# Connectors.net
KiCad netlist of a schematic drawn in Altium Designer
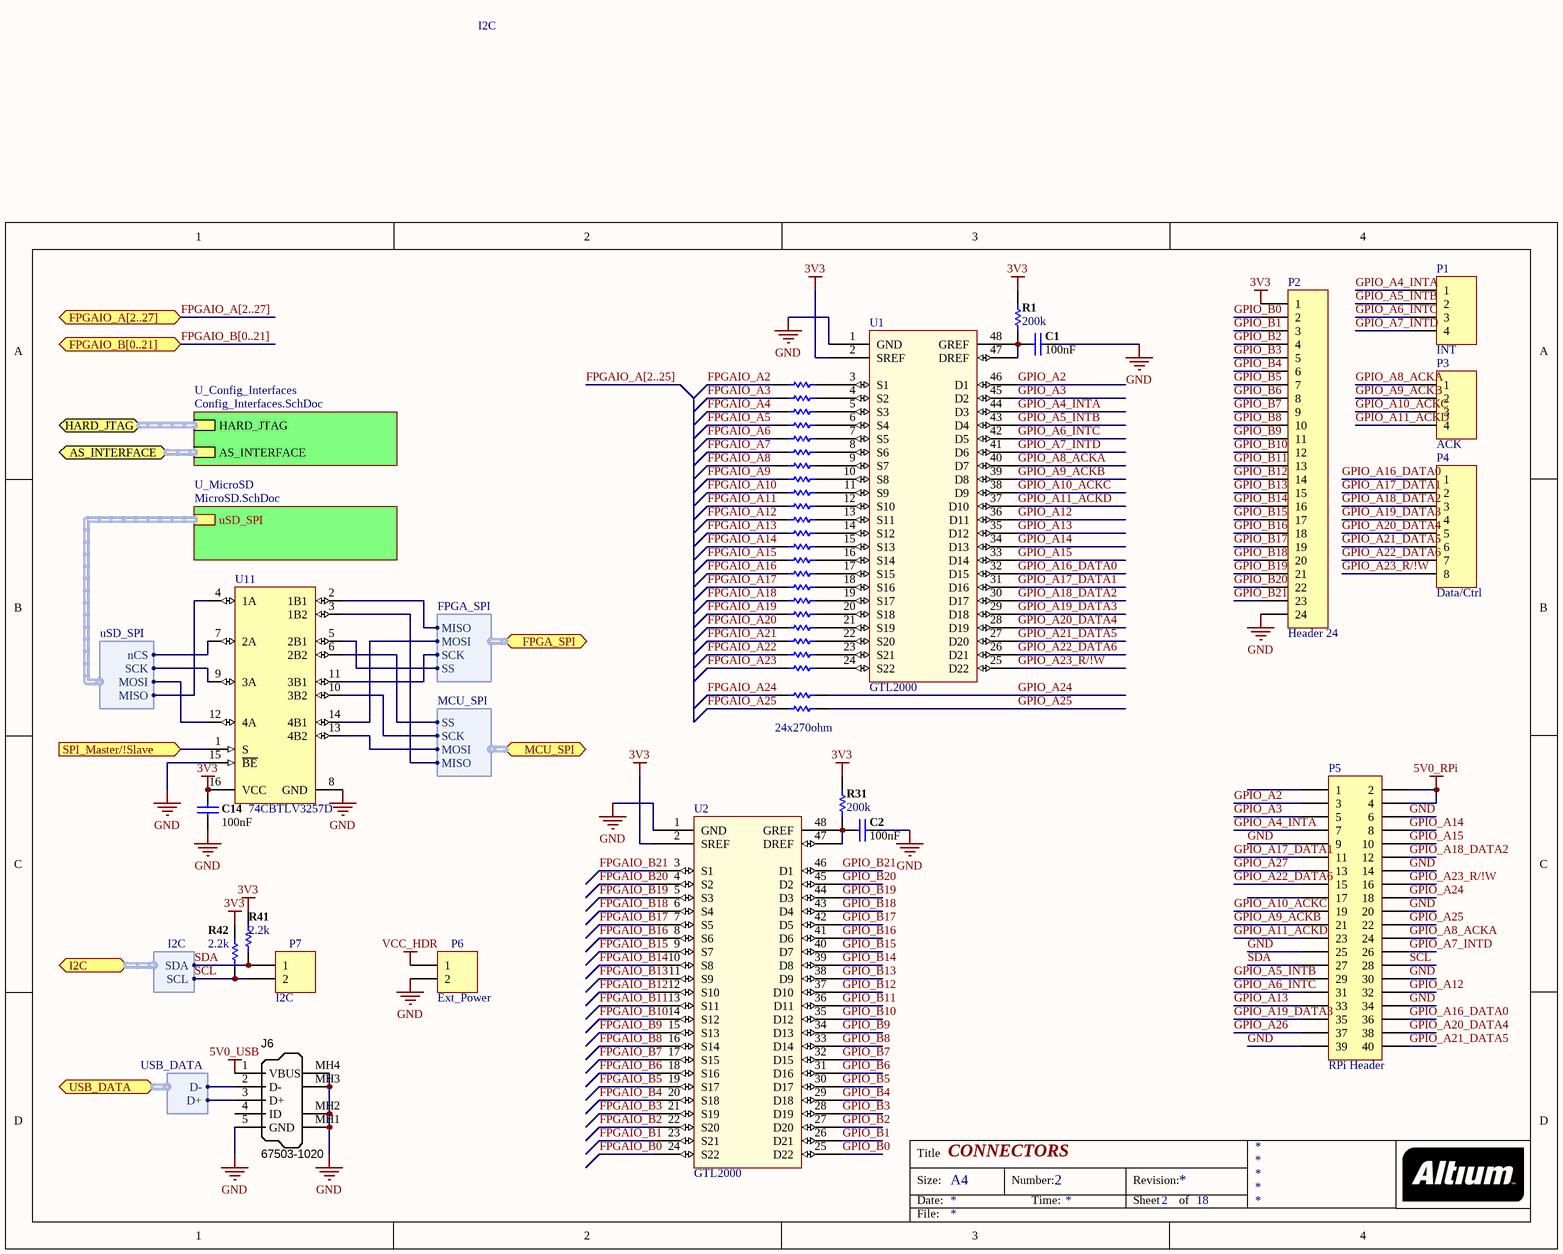
[diagram p0: Connectors.SchDoc]

(export (version "E")
  (design (tool "Eeschema 10.0.6"))
  (components
    (comp (ref "C1")
      (value "100nF")
      (footprint "0805C-GENERIC")
      (description "Capacitor, Ceramic, 10% 10V 0805 X7R")
      (fields (field (name "CAPACITANCE") "100nF") (field (name "TOLERANCE") "10 %"))
      (libsource (lib "altium-import") (part "root_1_CAP-NP_"))
    )
    (comp (ref "C2")
      (value "100nF")
      (footprint "0805C-GENERIC")
      (description "Capacitor, Ceramic, 10% 10V 0805 X7R")
      (fields (field (name "CAPACITANCE") "100nF") (field (name "TOLERANCE") "10 %"))
      (libsource (lib "altium-import") (part "root_1_CAP-NP_"))
    )
    (comp (ref "C14")
      (value "100nF")
      (footprint "0805C-GENERIC")
      (description "Capacitor, Ceramic, 10% 10V 0805 X7R")
      (fields (field (name "CAPACITANCE") "100nF") (field (name "TOLERANCE") "10 %"))
      (libsource (lib "altium-import") (part "root_0_CAP-NP_"))
    )
    (comp (ref "J6")
      (value "USB_Mini-B")
      (footprint "USB_Mini-B_Molex_SMT")
      (description "Connector SMD USB Type Mini-B")
      (fields (field (name "MANUFACTURER PART NUMBER 1") "67503-1020"))
      (libsource (lib "PBL - Connectors") (part "USB_Mini-B"))
    )
    (comp (ref "P1")
      (value "Header 4")
      (footprint "HEADER-1X4")
      (description "Header, 4-Pin")
      (fields (field (name "PUBLISHER") "Altium Limited"))
      (libsource (lib "Miscellaneous Connectors") (part "Header 4"))
    )
    (comp (ref "P2")
      (value "Header 24")
      (footprint "HDR1X24")
      (description "Header, 24-Pin")
      (fields (field (name "PUBLISHER") "Altium Limited"))
      (libsource (lib "Miscellaneous Connectors") (part "Header 24"))
    )
    (comp (ref "P3")
      (value "Header 4")
      (footprint "HEADER-1X4")
      (description "Header, 4-Pin")
      (fields (field (name "PUBLISHER") "Altium Limited"))
      (libsource (lib "Miscellaneous Connectors") (part "Header 4"))
    )
    (comp (ref "P4")
      (value "Header 8")
      (footprint "HEADER-1X8")
      (description "Header, 8-Pin")
      (fields (field (name "PUBLISHER") "Altium Limited"))
      (libsource (lib "Miscellaneous Connectors") (part "Header 8"))
    )
    (comp (ref "P5")
      (value "Header 20X2")
      (description "Header, 20-Pin, Dual row")
      (fields (field (name "PUBLISHER") "Altium Limited"))
      (libsource (lib "Miscellaneous Connectors") (part "Header 20X2"))
    )
    (comp (ref "P6")
      (value "Header 2")
      (footprint "Connector Molex 2")
      (description "Header, 2-Pin")
      (fields (field (name "PUBLISHER") "Altium Limited"))
      (libsource (lib "Miscellaneous Connectors") (part "Header 2"))
    )
    (comp (ref "P7")
      (value "Header 2")
      (footprint "HEADER-1X2")
      (description "Header, 2-Pin")
      (fields (field (name "PUBLISHER") "Altium Limited"))
      (libsource (lib "Miscellaneous Connectors") (part "Header 2"))
    )
    (comp (ref "R1")
      (value "200k")
      (footprint "0805R-220K")
      (fields (field (name "TOLERANCE") "1 %"))
      (libsource (lib "AltiumDesignLibrary") (part "RES"))
    )
    (comp (ref "R2")
      (value "270")
      (footprint "0805R-270")
      (fields (field (name "TOLERANCE") "1 %"))
      (libsource (lib "AltiumDesignLibrary") (part "RES"))
    )
    (comp (ref "R5")
      (value "270")
      (footprint "0805R-270")
      (fields (field (name "TOLERANCE") "1 %"))
      (libsource (lib "AltiumDesignLibrary") (part "RES"))
    )
    (comp (ref "R14")
      (value "270")
      (footprint "0805R-270")
      (fields (field (name "TOLERANCE") "1 %"))
      (libsource (lib "AltiumDesignLibrary") (part "RES"))
    )
    (comp (ref "R15")
      (value "270")
      (footprint "0805R-270")
      (fields (field (name "TOLERANCE") "1 %"))
      (libsource (lib "AltiumDesignLibrary") (part "RES"))
    )
    (comp (ref "R16")
      (value "270")
      (footprint "0805R-270")
      (fields (field (name "TOLERANCE") "1 %"))
      (libsource (lib "AltiumDesignLibrary") (part "RES"))
    )
    (comp (ref "R17")
      (value "270")
      (footprint "0805R-270")
      (fields (field (name "TOLERANCE") "1 %"))
      (libsource (lib "AltiumDesignLibrary") (part "RES"))
    )
    (comp (ref "R18")
      (value "270")
      (footprint "0805R-270")
      (fields (field (name "TOLERANCE") "1 %"))
      (libsource (lib "AltiumDesignLibrary") (part "RES"))
    )
    (comp (ref "R19")
      (value "270")
      (footprint "0805R-270")
      (fields (field (name "TOLERANCE") "1 %"))
      (libsource (lib "AltiumDesignLibrary") (part "RES"))
    )
    (comp (ref "R20")
      (value "270")
      (footprint "0805R-270")
      (fields (field (name "TOLERANCE") "1 %"))
      (libsource (lib "AltiumDesignLibrary") (part "RES"))
    )
    (comp (ref "R21")
      (value "270")
      (footprint "0805R-270")
      (fields (field (name "TOLERANCE") "1 %"))
      (libsource (lib "AltiumDesignLibrary") (part "RES"))
    )
    (comp (ref "R22")
      (value "270")
      (footprint "0805R-270")
      (fields (field (name "TOLERANCE") "1 %"))
      (libsource (lib "AltiumDesignLibrary") (part "RES"))
    )
    (comp (ref "R23")
      (value "270")
      (footprint "0805R-270")
      (fields (field (name "TOLERANCE") "1 %"))
      (libsource (lib "AltiumDesignLibrary") (part "RES"))
    )
    (comp (ref "R24")
      (value "270")
      (footprint "0805R-270")
      (fields (field (name "TOLERANCE") "1 %"))
      (libsource (lib "AltiumDesignLibrary") (part "RES"))
    )
    (comp (ref "R25")
      (value "270")
      (footprint "0805R-270")
      (fields (field (name "TOLERANCE") "1 %"))
      (libsource (lib "AltiumDesignLibrary") (part "RES"))
    )
    (comp (ref "R26")
      (value "270")
      (footprint "0805R-270")
      (fields (field (name "TOLERANCE") "1 %"))
      (libsource (lib "AltiumDesignLibrary") (part "RES"))
    )
    (comp (ref "R27")
      (value "270")
      (footprint "0805R-270")
      (fields (field (name "TOLERANCE") "1 %"))
      (libsource (lib "AltiumDesignLibrary") (part "RES"))
    )
    (comp (ref "R28")
      (value "270")
      (footprint "0805R-270")
      (fields (field (name "TOLERANCE") "1 %"))
      (libsource (lib "AltiumDesignLibrary") (part "RES"))
    )
    (comp (ref "R29")
      (value "270")
      (footprint "0805R-270")
      (fields (field (name "TOLERANCE") "1 %"))
      (libsource (lib "AltiumDesignLibrary") (part "RES"))
    )
    (comp (ref "R30")
      (value "270")
      (footprint "0805R-270")
      (fields (field (name "TOLERANCE") "1 %"))
      (libsource (lib "AltiumDesignLibrary") (part "RES"))
    )
    (comp (ref "R31")
      (value "200k")
      (footprint "0805R-220K")
      (fields (field (name "TOLERANCE") "1 %"))
      (libsource (lib "AltiumDesignLibrary") (part "RES"))
    )
    (comp (ref "R35")
      (value "270")
      (footprint "0805R-270")
      (fields (field (name "TOLERANCE") "1 %"))
      (libsource (lib "AltiumDesignLibrary") (part "RES"))
    )
    (comp (ref "R36")
      (value "270")
      (footprint "0805R-270")
      (fields (field (name "TOLERANCE") "1 %"))
      (libsource (lib "AltiumDesignLibrary") (part "RES"))
    )
    (comp (ref "R37")
      (value "270")
      (footprint "0805R-270")
      (fields (field (name "TOLERANCE") "1 %"))
      (libsource (lib "AltiumDesignLibrary") (part "RES"))
    )
    (comp (ref "R38")
      (value "270")
      (footprint "0805R-270")
      (fields (field (name "TOLERANCE") "1 %"))
      (libsource (lib "AltiumDesignLibrary") (part "RES"))
    )
    (comp (ref "R39")
      (value "270")
      (footprint "0805R-270")
      (fields (field (name "TOLERANCE") "1 %"))
      (libsource (lib "AltiumDesignLibrary") (part "RES"))
    )
    (comp (ref "R41")
      (value "2.2k")
      (footprint "0805R-0R1")
      (fields (field (name "TOLERANCE") "1 %"))
      (libsource (lib "AltiumDesignLibrary") (part "RES"))
    )
    (comp (ref "R42")
      (value "2.2k")
      (footprint "0805R-0R1")
      (fields (field (name "TOLERANCE") "1 %"))
      (libsource (lib "AltiumDesignLibrary") (part "RES"))
    )
    (comp (ref "U1")
      (value "GTL2000")
      (footprint "TSSOP50P810X120-48N")
      (description "22-bit bi-directional low voltage translator")
      (libsource (lib "My_components") (part "GTL2000"))
    )
    (comp (ref "U2")
      (value "GTL2000")
      (footprint "TSSOP50P810X120-48N")
      (description "22-bit bi-directional low voltage translator")
      (libsource (lib "My_components") (part "GTL2000"))
    )
    (comp (ref "U11")
      (value "74CBTLV3257D")
      (footprint "SO16")
      (fields (field (name "MANUFACTURER") "Analog Devices") (field (name "PARTNUMBER") "ADG3257BRQ"))
      (libsource (lib "Analog Devices Interface and Isolation Level Translators") (part "ADG3257BRQ"))
    )
  )
  (nets
    (net (code "11") (name "/D+") (class "Default")
      (node (ref "J6") (pin "3") (pinfunction "D+_3") (pintype "passive"))
    )
    (net (code "12") (name "/D-") (class "Default")
      (node (ref "J6") (pin "2") (pinfunction "D-_2") (pintype "passive"))
    )
    (net (code "13") (name "/FPGAIO_A2") (class "Default")
      (node (ref "R2") (pin "1") (pinfunction "1_1") (pintype "passive"))
    )
    (net (code "14") (name "/FPGAIO_A3") (class "Default")
      (node (ref "R5") (pin "1") (pinfunction "1_1") (pintype "passive"))
    )
    (net (code "15") (name "/FPGAIO_A4") (class "Default")
      (node (ref "R37") (pin "1") (pinfunction "1_1") (pintype "passive"))
    )
    (net (code "16") (name "/FPGAIO_A5") (class "Default")
      (node (ref "R38") (pin "1") (pinfunction "1_1") (pintype "passive"))
    )
    (net (code "17") (name "/FPGAIO_A6") (class "Default")
      (node (ref "R39") (pin "1") (pinfunction "1_1") (pintype "passive"))
    )
    (net (code "18") (name "/FPGAIO_A7") (class "Default")
      (node (ref "R14") (pin "1") (pinfunction "1_1") (pintype "passive"))
    )
    (net (code "19") (name "/FPGAIO_A8") (class "Default")
      (node (ref "R15") (pin "1") (pinfunction "1_1") (pintype "passive"))
    )
    (net (code "20") (name "/FPGAIO_A9") (class "Default")
      (node (ref "R16") (pin "1") (pinfunction "1_1") (pintype "passive"))
    )
    (net (code "21") (name "/FPGAIO_A10") (class "Default")
      (node (ref "R17") (pin "1") (pinfunction "1_1") (pintype "passive"))
    )
    (net (code "22") (name "/FPGAIO_A11") (class "Default")
      (node (ref "R18") (pin "1") (pinfunction "1_1") (pintype "passive"))
    )
    (net (code "23") (name "/FPGAIO_A12") (class "Default")
      (node (ref "R19") (pin "1") (pinfunction "1_1") (pintype "passive"))
    )
    (net (code "24") (name "/FPGAIO_A13") (class "Default")
      (node (ref "R20") (pin "1") (pinfunction "1_1") (pintype "passive"))
    )
    (net (code "25") (name "/FPGAIO_A14") (class "Default")
      (node (ref "R21") (pin "1") (pinfunction "1_1") (pintype "passive"))
    )
    (net (code "26") (name "/FPGAIO_A15") (class "Default")
      (node (ref "R22") (pin "1") (pinfunction "1_1") (pintype "passive"))
    )
    (net (code "27") (name "/FPGAIO_A16") (class "Default")
      (node (ref "R23") (pin "1") (pinfunction "1_1") (pintype "passive"))
    )
    (net (code "28") (name "/FPGAIO_A17") (class "Default")
      (node (ref "R24") (pin "1") (pinfunction "1_1") (pintype "passive"))
    )
    (net (code "29") (name "/FPGAIO_A18") (class "Default")
      (node (ref "R25") (pin "1") (pinfunction "1_1") (pintype "passive"))
    )
    (net (code "30") (name "/FPGAIO_A19") (class "Default")
      (node (ref "R26") (pin "1") (pinfunction "1_1") (pintype "passive"))
    )
    (net (code "31") (name "/FPGAIO_A20") (class "Default")
      (node (ref "R27") (pin "1") (pinfunction "1_1") (pintype "passive"))
    )
    (net (code "32") (name "/FPGAIO_A21") (class "Default")
      (node (ref "R28") (pin "1") (pinfunction "1_1") (pintype "passive"))
    )
    (net (code "33") (name "/FPGAIO_A22") (class "Default")
      (node (ref "R29") (pin "1") (pinfunction "1_1") (pintype "passive"))
    )
    (net (code "34") (name "/FPGAIO_A23") (class "Default")
      (node (ref "R30") (pin "1") (pinfunction "1_1") (pintype "passive"))
    )
    (net (code "35") (name "/FPGAIO_A24") (class "Default")
      (node (ref "R35") (pin "1") (pinfunction "1_1") (pintype "passive"))
    )
    (net (code "36") (name "/FPGAIO_A25") (class "Default")
      (node (ref "R36") (pin "1") (pinfunction "1_1") (pintype "passive"))
    )
    (net (code "39") (name "/FPGAIO_B0") (class "Default")
      (node (ref "U2") (pin "24") (pinfunction "S22_24") (pintype "bidirectional"))
    )
    (net (code "40") (name "/FPGAIO_B1") (class "Default")
      (node (ref "U2") (pin "23") (pinfunction "S21_23") (pintype "bidirectional"))
    )
    (net (code "41") (name "/FPGAIO_B2") (class "Default")
      (node (ref "U2") (pin "22") (pinfunction "S20_22") (pintype "bidirectional"))
    )
    (net (code "42") (name "/FPGAIO_B3") (class "Default")
      (node (ref "U2") (pin "21") (pinfunction "S19_21") (pintype "bidirectional"))
    )
    (net (code "43") (name "/FPGAIO_B4") (class "Default")
      (node (ref "U2") (pin "20") (pinfunction "S18_20") (pintype "bidirectional"))
    )
    (net (code "44") (name "/FPGAIO_B5") (class "Default")
      (node (ref "U2") (pin "19") (pinfunction "S17_19") (pintype "bidirectional"))
    )
    (net (code "45") (name "/FPGAIO_B6") (class "Default")
      (node (ref "U2") (pin "18") (pinfunction "S16_18") (pintype "bidirectional"))
    )
    (net (code "46") (name "/FPGAIO_B7") (class "Default")
      (node (ref "U2") (pin "17") (pinfunction "S15_17") (pintype "bidirectional"))
    )
    (net (code "47") (name "/FPGAIO_B8") (class "Default")
      (node (ref "U2") (pin "16") (pinfunction "S14_16") (pintype "bidirectional"))
    )
    (net (code "48") (name "/FPGAIO_B9") (class "Default")
      (node (ref "U2") (pin "15") (pinfunction "S13_15") (pintype "bidirectional"))
    )
    (net (code "49") (name "/FPGAIO_B10") (class "Default")
      (node (ref "U2") (pin "14") (pinfunction "S12_14") (pintype "bidirectional"))
    )
    (net (code "50") (name "/FPGAIO_B11") (class "Default")
      (node (ref "U2") (pin "13") (pinfunction "S11_13") (pintype "bidirectional"))
    )
    (net (code "51") (name "/FPGAIO_B12") (class "Default")
      (node (ref "U2") (pin "12") (pinfunction "S10_12") (pintype "bidirectional"))
    )
    (net (code "52") (name "/FPGAIO_B13") (class "Default")
      (node (ref "U2") (pin "11") (pinfunction "S9_11") (pintype "bidirectional"))
    )
    (net (code "53") (name "/FPGAIO_B14") (class "Default")
      (node (ref "U2") (pin "10") (pinfunction "S8_10") (pintype "bidirectional"))
    )
    (net (code "54") (name "/FPGAIO_B15") (class "Default")
      (node (ref "U2") (pin "9") (pinfunction "S7_9") (pintype "bidirectional"))
    )
    (net (code "55") (name "/FPGAIO_B16") (class "Default")
      (node (ref "U2") (pin "8") (pinfunction "S6_8") (pintype "bidirectional"))
    )
    (net (code "56") (name "/FPGAIO_B17") (class "Default")
      (node (ref "U2") (pin "7") (pinfunction "S5_7") (pintype "bidirectional"))
    )
    (net (code "57") (name "/FPGAIO_B18") (class "Default")
      (node (ref "U2") (pin "6") (pinfunction "S4_6") (pintype "bidirectional"))
    )
    (net (code "58") (name "/FPGAIO_B19") (class "Default")
      (node (ref "U2") (pin "5") (pinfunction "S3_5") (pintype "bidirectional"))
    )
    (net (code "59") (name "/FPGAIO_B20") (class "Default")
      (node (ref "U2") (pin "4") (pinfunction "S2_4") (pintype "bidirectional"))
    )
    (net (code "60") (name "/FPGAIO_B21") (class "Default")
      (node (ref "U2") (pin "3") (pinfunction "S1_3") (pintype "bidirectional"))
    )
    (net (code "62") (name "/GPIO_A2") (class "Default")
      (node (ref "P5") (pin "3") (pinfunction "3_3") (pintype "passive"))
      (node (ref "U1") (pin "46") (pinfunction "D1_46") (pintype "bidirectional"))
    )
    (net (code "63") (name "/GPIO_A3") (class "Default")
      (node (ref "P5") (pin "5") (pinfunction "5_5") (pintype "passive"))
      (node (ref "U1") (pin "45") (pinfunction "D2_45") (pintype "bidirectional"))
    )
    (net (code "64") (name "/GPIO_A4_INTA") (class "Default")
      (node (ref "P1") (pin "1") (pinfunction "1_1") (pintype "passive"))
      (node (ref "P5") (pin "7") (pinfunction "7_7") (pintype "passive"))
      (node (ref "U1") (pin "44") (pinfunction "D3_44") (pintype "bidirectional"))
    )
    (net (code "65") (name "/GPIO_A5_INTB") (class "Default")
      (node (ref "P1") (pin "2") (pinfunction "2_2") (pintype "passive"))
      (node (ref "P5") (pin "29") (pinfunction "29_29") (pintype "passive"))
      (node (ref "U1") (pin "43") (pinfunction "D4_43") (pintype "bidirectional"))
    )
    (net (code "66") (name "/GPIO_A6_INTC") (class "Default")
      (node (ref "P1") (pin "3") (pinfunction "3_3") (pintype "passive"))
      (node (ref "P5") (pin "31") (pinfunction "31_31") (pintype "passive"))
      (node (ref "U1") (pin "42") (pinfunction "D5_42") (pintype "bidirectional"))
    )
    (net (code "67") (name "/GPIO_A7_INTD") (class "Default")
      (node (ref "P1") (pin "4") (pinfunction "4_4") (pintype "passive"))
      (node (ref "P5") (pin "26") (pinfunction "26_26") (pintype "passive"))
      (node (ref "U1") (pin "41") (pinfunction "D6_41") (pintype "bidirectional"))
    )
    (net (code "68") (name "/GPIO_A8_ACKA") (class "Default")
      (node (ref "P3") (pin "1") (pinfunction "1_1") (pintype "passive"))
      (node (ref "P5") (pin "24") (pinfunction "24_24") (pintype "passive"))
      (node (ref "U1") (pin "40") (pinfunction "D7_40") (pintype "bidirectional"))
    )
    (net (code "69") (name "/GPIO_A9_ACKB") (class "Default")
      (node (ref "P3") (pin "2") (pinfunction "2_2") (pintype "passive"))
      (node (ref "P5") (pin "21") (pinfunction "21_21") (pintype "passive"))
      (node (ref "U1") (pin "39") (pinfunction "D8_39") (pintype "bidirectional"))
    )
    (net (code "70") (name "/GPIO_A10_ACKC") (class "Default")
      (node (ref "P3") (pin "3") (pinfunction "3_3") (pintype "passive"))
      (node (ref "P5") (pin "19") (pinfunction "19_19") (pintype "passive"))
      (node (ref "U1") (pin "38") (pinfunction "D9_38") (pintype "bidirectional"))
    )
    (net (code "71") (name "/GPIO_A11_ACKD") (class "Default")
      (node (ref "P3") (pin "4") (pinfunction "4_4") (pintype "passive"))
      (node (ref "P5") (pin "23") (pinfunction "23_23") (pintype "passive"))
      (node (ref "U1") (pin "37") (pinfunction "D10_37") (pintype "bidirectional"))
    )
    (net (code "72") (name "/GPIO_A12") (class "Default")
      (node (ref "P5") (pin "32") (pinfunction "32_32") (pintype "passive"))
      (node (ref "U1") (pin "36") (pinfunction "D11_36") (pintype "bidirectional"))
    )
    (net (code "73") (name "/GPIO_A13") (class "Default")
      (node (ref "P5") (pin "33") (pinfunction "33_33") (pintype "passive"))
      (node (ref "U1") (pin "35") (pinfunction "D12_35") (pintype "bidirectional"))
    )
    (net (code "74") (name "/GPIO_A14") (class "Default")
      (node (ref "P5") (pin "8") (pinfunction "8_8") (pintype "passive"))
      (node (ref "U1") (pin "34") (pinfunction "D13_34") (pintype "bidirectional"))
    )
    (net (code "75") (name "/GPIO_A15") (class "Default")
      (node (ref "P5") (pin "10") (pinfunction "10_10") (pintype "passive"))
      (node (ref "U1") (pin "33") (pinfunction "D14_33") (pintype "bidirectional"))
    )
    (net (code "76") (name "/GPIO_A16_DATA0") (class "Default")
      (node (ref "P4") (pin "1") (pinfunction "1_1") (pintype "passive"))
      (node (ref "P5") (pin "36") (pinfunction "36_36") (pintype "passive"))
      (node (ref "U1") (pin "32") (pinfunction "D15_32") (pintype "bidirectional"))
    )
    (net (code "77") (name "/GPIO_A17_DATA1") (class "Default")
      (node (ref "P4") (pin "2") (pinfunction "2_2") (pintype "passive"))
      (node (ref "P5") (pin "11") (pinfunction "11_11") (pintype "passive"))
      (node (ref "U1") (pin "31") (pinfunction "D16_31") (pintype "bidirectional"))
    )
    (net (code "78") (name "/GPIO_A18_DATA2") (class "Default")
      (node (ref "P4") (pin "3") (pinfunction "3_3") (pintype "passive"))
      (node (ref "P5") (pin "12") (pinfunction "12_12") (pintype "passive"))
      (node (ref "U1") (pin "30") (pinfunction "D17_30") (pintype "bidirectional"))
    )
    (net (code "79") (name "/GPIO_A19_DATA3") (class "Default")
      (node (ref "P4") (pin "4") (pinfunction "4_4") (pintype "passive"))
      (node (ref "P5") (pin "35") (pinfunction "35_35") (pintype "passive"))
      (node (ref "U1") (pin "29") (pinfunction "D18_29") (pintype "bidirectional"))
    )
    (net (code "80") (name "/GPIO_A20_DATA4") (class "Default")
      (node (ref "P4") (pin "5") (pinfunction "5_5") (pintype "passive"))
      (node (ref "P5") (pin "38") (pinfunction "38_38") (pintype "passive"))
      (node (ref "U1") (pin "28") (pinfunction "D19_28") (pintype "bidirectional"))
    )
    (net (code "81") (name "/GPIO_A21_DATA5") (class "Default")
      (node (ref "P4") (pin "6") (pinfunction "6_6") (pintype "passive"))
      (node (ref "P5") (pin "40") (pinfunction "40_40") (pintype "passive"))
      (node (ref "U1") (pin "27") (pinfunction "D20_27") (pintype "bidirectional"))
    )
    (net (code "82") (name "/GPIO_A22_DATA6") (class "Default")
      (node (ref "P4") (pin "7") (pinfunction "7_7") (pintype "passive"))
      (node (ref "P5") (pin "15") (pinfunction "15_15") (pintype "passive"))
      (node (ref "U1") (pin "26") (pinfunction "D21_26") (pintype "bidirectional"))
    )
    (net (code "83") (name "/GPIO_A23_R{slash}!W") (class "Default")
      (node (ref "P4") (pin "8") (pinfunction "8_8") (pintype "passive"))
      (node (ref "P5") (pin "16") (pinfunction "16_16") (pintype "passive"))
      (node (ref "U1") (pin "25") (pinfunction "D22_25") (pintype "bidirectional"))
    )
    (net (code "84") (name "/GPIO_A24") (class "Default")
      (node (ref "P5") (pin "18") (pinfunction "18_18") (pintype "passive"))
      (node (ref "R35") (pin "2") (pinfunction "2_2") (pintype "passive"))
    )
    (net (code "85") (name "/GPIO_A25") (class "Default")
      (node (ref "P5") (pin "22") (pinfunction "22_22") (pintype "passive"))
      (node (ref "R36") (pin "2") (pinfunction "2_2") (pintype "passive"))
    )
    (net (code "86") (name "/GPIO_A26") (class "Default")
      (node (ref "P5") (pin "37") (pinfunction "37_37") (pintype "passive"))
    )
    (net (code "87") (name "/GPIO_A27") (class "Default")
      (node (ref "P5") (pin "13") (pinfunction "13_13") (pintype "passive"))
    )
    (net (code "88") (name "/GPIO_B0") (class "Default")
      (node (ref "P2") (pin "2") (pinfunction "2_2") (pintype "passive"))
      (node (ref "U2") (pin "25") (pinfunction "D22_25") (pintype "bidirectional"))
    )
    (net (code "89") (name "/GPIO_B1") (class "Default")
      (node (ref "P2") (pin "3") (pinfunction "3_3") (pintype "passive"))
      (node (ref "U2") (pin "26") (pinfunction "D21_26") (pintype "bidirectional"))
    )
    (net (code "90") (name "/GPIO_B2") (class "Default")
      (node (ref "P2") (pin "4") (pinfunction "4_4") (pintype "passive"))
      (node (ref "U2") (pin "27") (pinfunction "D20_27") (pintype "bidirectional"))
    )
    (net (code "91") (name "/GPIO_B3") (class "Default")
      (node (ref "P2") (pin "5") (pinfunction "5_5") (pintype "passive"))
      (node (ref "U2") (pin "28") (pinfunction "D19_28") (pintype "bidirectional"))
    )
    (net (code "92") (name "/GPIO_B4") (class "Default")
      (node (ref "P2") (pin "6") (pinfunction "6_6") (pintype "passive"))
      (node (ref "U2") (pin "29") (pinfunction "D18_29") (pintype "bidirectional"))
    )
    (net (code "93") (name "/GPIO_B5") (class "Default")
      (node (ref "P2") (pin "7") (pinfunction "7_7") (pintype "passive"))
      (node (ref "U2") (pin "30") (pinfunction "D17_30") (pintype "bidirectional"))
    )
    (net (code "94") (name "/GPIO_B6") (class "Default")
      (node (ref "P2") (pin "8") (pinfunction "8_8") (pintype "passive"))
      (node (ref "U2") (pin "31") (pinfunction "D16_31") (pintype "bidirectional"))
    )
    (net (code "95") (name "/GPIO_B7") (class "Default")
      (node (ref "P2") (pin "9") (pinfunction "9_9") (pintype "passive"))
      (node (ref "U2") (pin "32") (pinfunction "D15_32") (pintype "bidirectional"))
    )
    (net (code "96") (name "/GPIO_B8") (class "Default")
      (node (ref "P2") (pin "10") (pinfunction "10_10") (pintype "passive"))
      (node (ref "U2") (pin "33") (pinfunction "D14_33") (pintype "bidirectional"))
    )
    (net (code "97") (name "/GPIO_B9") (class "Default")
      (node (ref "P2") (pin "11") (pinfunction "11_11") (pintype "passive"))
      (node (ref "U2") (pin "34") (pinfunction "D13_34") (pintype "bidirectional"))
    )
    (net (code "98") (name "/GPIO_B10") (class "Default")
      (node (ref "P2") (pin "12") (pinfunction "12_12") (pintype "passive"))
      (node (ref "U2") (pin "35") (pinfunction "D12_35") (pintype "bidirectional"))
    )
    (net (code "99") (name "/GPIO_B11") (class "Default")
      (node (ref "P2") (pin "13") (pinfunction "13_13") (pintype "passive"))
      (node (ref "U2") (pin "36") (pinfunction "D11_36") (pintype "bidirectional"))
    )
    (net (code "100") (name "/GPIO_B12") (class "Default")
      (node (ref "P2") (pin "14") (pinfunction "14_14") (pintype "passive"))
      (node (ref "U2") (pin "37") (pinfunction "D10_37") (pintype "bidirectional"))
    )
    (net (code "101") (name "/GPIO_B13") (class "Default")
      (node (ref "P2") (pin "15") (pinfunction "15_15") (pintype "passive"))
      (node (ref "U2") (pin "38") (pinfunction "D9_38") (pintype "bidirectional"))
    )
    (net (code "102") (name "/GPIO_B14") (class "Default")
      (node (ref "P2") (pin "16") (pinfunction "16_16") (pintype "passive"))
      (node (ref "U2") (pin "39") (pinfunction "D8_39") (pintype "bidirectional"))
    )
    (net (code "103") (name "/GPIO_B15") (class "Default")
      (node (ref "P2") (pin "17") (pinfunction "17_17") (pintype "passive"))
      (node (ref "U2") (pin "40") (pinfunction "D7_40") (pintype "bidirectional"))
    )
    (net (code "104") (name "/GPIO_B16") (class "Default")
      (node (ref "P2") (pin "18") (pinfunction "18_18") (pintype "passive"))
      (node (ref "U2") (pin "41") (pinfunction "D6_41") (pintype "bidirectional"))
    )
    (net (code "105") (name "/GPIO_B17") (class "Default")
      (node (ref "P2") (pin "19") (pinfunction "19_19") (pintype "passive"))
      (node (ref "U2") (pin "42") (pinfunction "D5_42") (pintype "bidirectional"))
    )
    (net (code "106") (name "/GPIO_B18") (class "Default")
      (node (ref "P2") (pin "20") (pinfunction "20_20") (pintype "passive"))
      (node (ref "U2") (pin "43") (pinfunction "D4_43") (pintype "bidirectional"))
    )
    (net (code "107") (name "/GPIO_B19") (class "Default")
      (node (ref "P2") (pin "21") (pinfunction "21_21") (pintype "passive"))
      (node (ref "U2") (pin "44") (pinfunction "D3_44") (pintype "bidirectional"))
    )
    (net (code "108") (name "/GPIO_B20") (class "Default")
      (node (ref "P2") (pin "22") (pinfunction "22_22") (pintype "passive"))
      (node (ref "U2") (pin "45") (pinfunction "D2_45") (pintype "bidirectional"))
    )
    (net (code "109") (name "/GPIO_B21") (class "Default")
      (node (ref "P2") (pin "23") (pinfunction "23_23") (pintype "passive"))
      (node (ref "U2") (pin "46") (pinfunction "D1_46") (pintype "bidirectional"))
    )
    (net (code "111") (name "/SCL") (class "Default")
      (node (ref "P5") (pin "28") (pinfunction "28_28") (pintype "passive"))
      (node (ref "P7") (pin "2") (pinfunction "2_2") (pintype "passive"))
      (node (ref "R42") (pin "2") (pinfunction "2_2") (pintype "passive"))
    )
    (net (code "112") (name "/SDA") (class "Default")
      (node (ref "P5") (pin "27") (pinfunction "27_27") (pintype "passive"))
      (node (ref "P7") (pin "1") (pinfunction "1_1") (pintype "passive"))
      (node (ref "R41") (pin "2") (pinfunction "2_2") (pintype "passive"))
    )
    (net (code "113") (name "/SPI_Master{slash}!Slave") (class "Default")
      (node (ref "U11") (pin "1") (pinfunction "S_1") (pintype "input"))
    )
    (net (code "114") (name "/nCS") (class "Default")
      (node (ref "U11") (pin "7") (pinfunction "2A_7") (pintype "bidirectional"))
    )
    (net (code "120") (name "3V3") (class "Default")
      (node (ref "C14") (pin "1") (pinfunction "1_1") (pintype "passive"))
      (node (ref "P2") (pin "1") (pinfunction "1_1") (pintype "passive"))
      (node (ref "R1") (pin "2") (pinfunction "2_2") (pintype "passive"))
      (node (ref "R31") (pin "2") (pinfunction "2_2") (pintype "passive"))
      (node (ref "R41") (pin "1") (pinfunction "1_1") (pintype "passive"))
      (node (ref "R42") (pin "1") (pinfunction "1_1") (pintype "passive"))
      (node (ref "U1") (pin "2") (pinfunction "SREF_2") (pintype "power_in"))
      (node (ref "U11") (pin "16") (pinfunction "VCC_16") (pintype "power_in"))
      (node (ref "U2") (pin "2") (pinfunction "SREF_2") (pintype "power_in"))
    )
    (net (code "121") (name "5V0_RPi") (class "Default")
      (node (ref "P5") (pin "2") (pinfunction "2_2") (pintype "passive"))
      (node (ref "P5") (pin "4") (pinfunction "4_4") (pintype "passive"))
    )
    (net (code "122") (name "5V0_USB") (class "Default")
      (node (ref "J6") (pin "1") (pinfunction "VBUS_1") (pintype "passive"))
    )
    (net (code "123") (name "GND") (class "Default")
      (node (ref "C1") (pin "2") (pinfunction "2_2") (pintype "passive"))
      (node (ref "C14") (pin "2") (pinfunction "2_2") (pintype "passive"))
      (node (ref "C2") (pin "2") (pinfunction "2_2") (pintype "passive"))
      (node (ref "J6") (pin "5") (pinfunction "GND_5") (pintype "passive"))
      (node (ref "J6") (pin "MH1") (pinfunction "Shell_MH1") (pintype "passive"))
      (node (ref "J6") (pin "MH2") (pinfunction "Shell_MH2") (pintype "passive"))
      (node (ref "J6") (pin "MH3") (pinfunction "Shell_MH3") (pintype "passive"))
      (node (ref "J6") (pin "MH4") (pinfunction "Shell_MH4") (pintype "passive"))
      (node (ref "P2") (pin "24") (pinfunction "24_24") (pintype "passive"))
      (node (ref "P5") (pin "14") (pinfunction "14_14") (pintype "passive"))
      (node (ref "P5") (pin "20") (pinfunction "20_20") (pintype "passive"))
      (node (ref "P5") (pin "25") (pinfunction "25_25") (pintype "passive"))
      (node (ref "P5") (pin "30") (pinfunction "30_30") (pintype "passive"))
      (node (ref "P5") (pin "34") (pinfunction "34_34") (pintype "passive"))
      (node (ref "P5") (pin "39") (pinfunction "39_39") (pintype "passive"))
      (node (ref "P5") (pin "6") (pinfunction "6_6") (pintype "passive"))
      (node (ref "P5") (pin "9") (pinfunction "9_9") (pintype "passive"))
      (node (ref "P6") (pin "2") (pinfunction "2_2") (pintype "passive"))
      (node (ref "U1") (pin "1") (pinfunction "GND_1") (pintype "passive"))
      (node (ref "U11") (pin "15") (pinfunction "~{BE}_15") (pintype "input"))
      (node (ref "U11") (pin "8") (pinfunction "GND_8") (pintype "power_in"))
      (node (ref "U2") (pin "1") (pinfunction "GND_1") (pintype "passive"))
    )
    (net (code "124") (name "Net-(U1-DREF)") (class "Default")
      (node (ref "C1") (pin "1") (pinfunction "1_1") (pintype "passive"))
      (node (ref "R1") (pin "1") (pinfunction "1_1") (pintype "passive"))
      (node (ref "U1") (pin "47") (pinfunction "DREF_47") (pintype "bidirectional"))
      (node (ref "U1") (pin "48") (pinfunction "GREF_48") (pintype "power_in"))
    )
    (net (code "125") (name "Net-(U1-S1)") (class "Default")
      (node (ref "R2") (pin "2") (pinfunction "2_2") (pintype "passive"))
      (node (ref "U1") (pin "3") (pinfunction "S1_3") (pintype "bidirectional"))
    )
    (net (code "126") (name "Net-(U1-S2)") (class "Default")
      (node (ref "R5") (pin "2") (pinfunction "2_2") (pintype "passive"))
      (node (ref "U1") (pin "4") (pinfunction "S2_4") (pintype "bidirectional"))
    )
    (net (code "127") (name "Net-(U1-S3)") (class "Default")
      (node (ref "R37") (pin "2") (pinfunction "2_2") (pintype "passive"))
      (node (ref "U1") (pin "5") (pinfunction "S3_5") (pintype "bidirectional"))
    )
    (net (code "128") (name "Net-(U1-S4)") (class "Default")
      (node (ref "R38") (pin "2") (pinfunction "2_2") (pintype "passive"))
      (node (ref "U1") (pin "6") (pinfunction "S4_6") (pintype "bidirectional"))
    )
    (net (code "129") (name "Net-(U1-S5)") (class "Default")
      (node (ref "R39") (pin "2") (pinfunction "2_2") (pintype "passive"))
      (node (ref "U1") (pin "7") (pinfunction "S5_7") (pintype "bidirectional"))
    )
    (net (code "130") (name "Net-(U1-S6)") (class "Default")
      (node (ref "R14") (pin "2") (pinfunction "2_2") (pintype "passive"))
      (node (ref "U1") (pin "8") (pinfunction "S6_8") (pintype "bidirectional"))
    )
    (net (code "131") (name "Net-(U1-S7)") (class "Default")
      (node (ref "R15") (pin "2") (pinfunction "2_2") (pintype "passive"))
      (node (ref "U1") (pin "9") (pinfunction "S7_9") (pintype "bidirectional"))
    )
    (net (code "132") (name "Net-(U1-S8)") (class "Default")
      (node (ref "R16") (pin "2") (pinfunction "2_2") (pintype "passive"))
      (node (ref "U1") (pin "10") (pinfunction "S8_10") (pintype "bidirectional"))
    )
    (net (code "133") (name "Net-(U1-S9)") (class "Default")
      (node (ref "R17") (pin "2") (pinfunction "2_2") (pintype "passive"))
      (node (ref "U1") (pin "11") (pinfunction "S9_11") (pintype "bidirectional"))
    )
    (net (code "134") (name "Net-(U1-S10)") (class "Default")
      (node (ref "R18") (pin "2") (pinfunction "2_2") (pintype "passive"))
      (node (ref "U1") (pin "12") (pinfunction "S10_12") (pintype "bidirectional"))
    )
    (net (code "135") (name "Net-(U1-S11)") (class "Default")
      (node (ref "R19") (pin "2") (pinfunction "2_2") (pintype "passive"))
      (node (ref "U1") (pin "13") (pinfunction "S11_13") (pintype "bidirectional"))
    )
    (net (code "136") (name "Net-(U1-S12)") (class "Default")
      (node (ref "R20") (pin "2") (pinfunction "2_2") (pintype "passive"))
      (node (ref "U1") (pin "14") (pinfunction "S12_14") (pintype "bidirectional"))
    )
    (net (code "137") (name "Net-(U1-S13)") (class "Default")
      (node (ref "R21") (pin "2") (pinfunction "2_2") (pintype "passive"))
      (node (ref "U1") (pin "15") (pinfunction "S13_15") (pintype "bidirectional"))
    )
    (net (code "138") (name "Net-(U1-S14)") (class "Default")
      (node (ref "R22") (pin "2") (pinfunction "2_2") (pintype "passive"))
      (node (ref "U1") (pin "16") (pinfunction "S14_16") (pintype "bidirectional"))
    )
    (net (code "139") (name "Net-(U1-S15)") (class "Default")
      (node (ref "R23") (pin "2") (pinfunction "2_2") (pintype "passive"))
      (node (ref "U1") (pin "17") (pinfunction "S15_17") (pintype "bidirectional"))
    )
    (net (code "140") (name "Net-(U1-S16)") (class "Default")
      (node (ref "R24") (pin "2") (pinfunction "2_2") (pintype "passive"))
      (node (ref "U1") (pin "18") (pinfunction "S16_18") (pintype "bidirectional"))
    )
    (net (code "141") (name "Net-(U1-S17)") (class "Default")
      (node (ref "R25") (pin "2") (pinfunction "2_2") (pintype "passive"))
      (node (ref "U1") (pin "19") (pinfunction "S17_19") (pintype "bidirectional"))
    )
    (net (code "142") (name "Net-(U1-S18)") (class "Default")
      (node (ref "R26") (pin "2") (pinfunction "2_2") (pintype "passive"))
      (node (ref "U1") (pin "20") (pinfunction "S18_20") (pintype "bidirectional"))
    )
    (net (code "143") (name "Net-(U1-S19)") (class "Default")
      (node (ref "R27") (pin "2") (pinfunction "2_2") (pintype "passive"))
      (node (ref "U1") (pin "21") (pinfunction "S19_21") (pintype "bidirectional"))
    )
    (net (code "144") (name "Net-(U1-S20)") (class "Default")
      (node (ref "R28") (pin "2") (pinfunction "2_2") (pintype "passive"))
      (node (ref "U1") (pin "22") (pinfunction "S20_22") (pintype "bidirectional"))
    )
    (net (code "145") (name "Net-(U1-S21)") (class "Default")
      (node (ref "R29") (pin "2") (pinfunction "2_2") (pintype "passive"))
      (node (ref "U1") (pin "23") (pinfunction "S21_23") (pintype "bidirectional"))
    )
    (net (code "146") (name "Net-(U1-S22)") (class "Default")
      (node (ref "R30") (pin "2") (pinfunction "2_2") (pintype "passive"))
      (node (ref "U1") (pin "24") (pinfunction "S22_24") (pintype "bidirectional"))
    )
    (net (code "147") (name "Net-(U2-DREF)") (class "Default")
      (node (ref "C2") (pin "1") (pinfunction "1_1") (pintype "passive"))
      (node (ref "R31") (pin "1") (pinfunction "1_1") (pintype "passive"))
      (node (ref "U2") (pin "47") (pinfunction "DREF_47") (pintype "bidirectional"))
      (node (ref "U2") (pin "48") (pinfunction "GREF_48") (pintype "power_in"))
    )
    (net (code "148") (name "VCC_HDR") (class "Default")
      (node (ref "P6") (pin "1") (pinfunction "1_1") (pintype "passive"))
    )
    (net (code "149") (name "unconnected-(J6-ID-Pad4)") (class "Default")
      (node (ref "J6") (pin "4") (pinfunction "ID_4") (pintype "passive"))
    )
    (net (code "150") (name "unconnected-(P5-Pad1)") (class "Default")
      (node (ref "P5") (pin "1") (pinfunction "1_1") (pintype "passive"))
    )
    (net (code "151") (name "unconnected-(P5-Pad17)") (class "Default")
      (node (ref "P5") (pin "17") (pinfunction "17_17") (pintype "passive"))
    )
    (net (code "152") (name "unconnected-(U11-1A-Pad4)") (class "Default")
      (node (ref "U11") (pin "4") (pinfunction "1A_4") (pintype "bidirectional"))
    )
    (net (code "153") (name "unconnected-(U11-1B1-Pad2)") (class "Default")
      (node (ref "U11") (pin "2") (pinfunction "1B1_2") (pintype "bidirectional"))
    )
    (net (code "154") (name "unconnected-(U11-1B2-Pad3)") (class "Default")
      (node (ref "U11") (pin "3") (pinfunction "1B2_3") (pintype "bidirectional"))
    )
    (net (code "155") (name "unconnected-(U11-2B1-Pad5)") (class "Default")
      (node (ref "U11") (pin "5") (pinfunction "2B1_5") (pintype "bidirectional"))
    )
    (net (code "156") (name "unconnected-(U11-2B2-Pad6)") (class "Default")
      (node (ref "U11") (pin "6") (pinfunction "2B2_6") (pintype "bidirectional"))
    )
    (net (code "157") (name "unconnected-(U11-3A-Pad9)") (class "Default")
      (node (ref "U11") (pin "9") (pinfunction "3A_9") (pintype "bidirectional"))
    )
    (net (code "158") (name "unconnected-(U11-3B1-Pad11)") (class "Default")
      (node (ref "U11") (pin "11") (pinfunction "3B1_11") (pintype "bidirectional"))
    )
    (net (code "159") (name "unconnected-(U11-3B2-Pad10)") (class "Default")
      (node (ref "U11") (pin "10") (pinfunction "3B2_10") (pintype "bidirectional"))
    )
    (net (code "160") (name "unconnected-(U11-4A-Pad12)") (class "Default")
      (node (ref "U11") (pin "12") (pinfunction "4A_12") (pintype "bidirectional"))
    )
    (net (code "161") (name "unconnected-(U11-4B1-Pad14)") (class "Default")
      (node (ref "U11") (pin "14") (pinfunction "4B1_14") (pintype "bidirectional"))
    )
    (net (code "162") (name "unconnected-(U11-4B2-Pad13)") (class "Default")
      (node (ref "U11") (pin "13") (pinfunction "4B2_13") (pintype "bidirectional"))
    )
  )
)
